# ADC5G_FRONTEND.net
KiCad netlist of a schematic drawn in Altium Designer
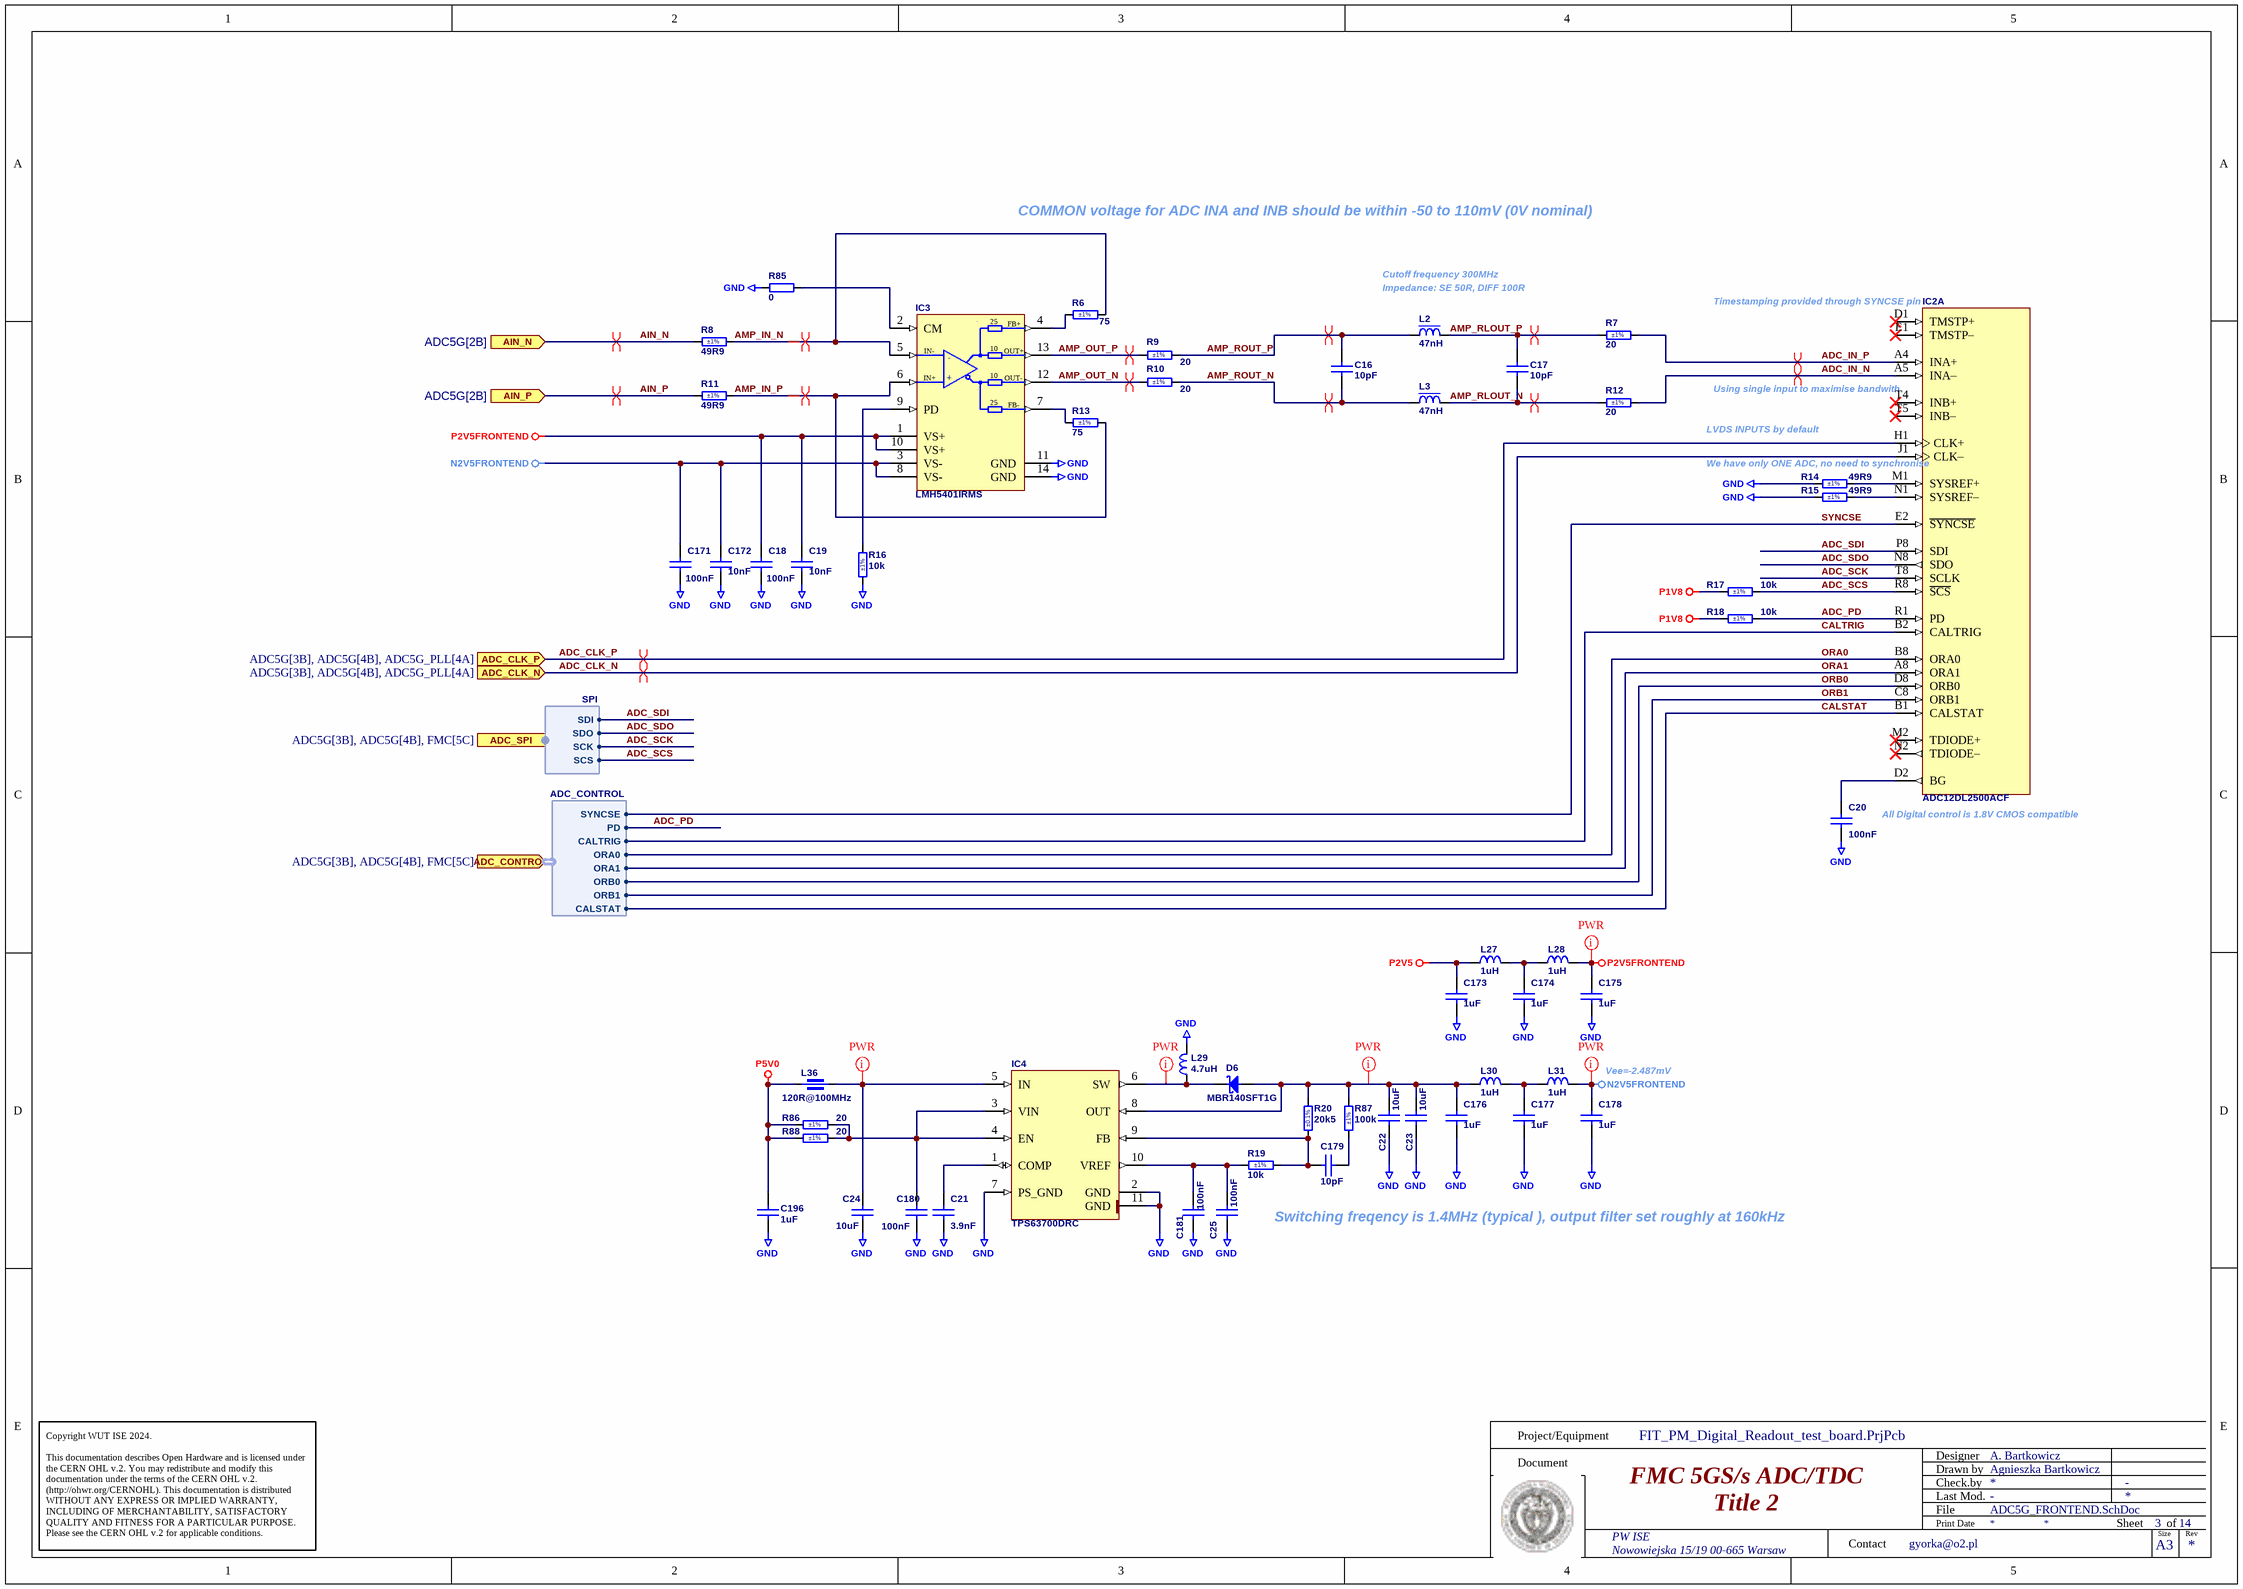
[diagram p0: ADC5G_FRONTEND.SchDoc]

(export (version "E")
  (design (tool "Eeschema 10.0.6"))
  (components
    (comp (ref "C16")
      (value "10pF")
      (footprint "CAPC1005X55N")
      (description "Non-polarised capacitor")
      (fields
        (field (name "PART NUMBER") "CC0402_10PF_50V_5%_C0G")
        (field (name "VOLTAGE") "50V")
        (field (name "AUTHOR") "CERN DEM JLC")
      )
      (libsource (lib "Capacitors") (part "Capacitor - non polarized"))
    )
    (comp (ref "C17")
      (value "10pF")
      (footprint "CAPC1005X55N")
      (description "Non-polarised capacitor")
      (fields
        (field (name "PART NUMBER") "CC0402_10PF_50V_5%_C0G")
        (field (name "VOLTAGE") "50V")
        (field (name "AUTHOR") "CERN DEM JLC")
      )
      (libsource (lib "Capacitors") (part "Capacitor - non polarized"))
    )
    (comp (ref "C18")
      (value "100nF")
      (footprint "CAPC1005X55N")
      (description "Non-polarised capacitor")
      (fields
        (field (name "PART NUMBER") "CC0402_100NF_16V_10%_X5R")
        (field (name "VOLTAGE") "16V")
        (field (name "AUTHOR") "CERN DEM JLC")
      )
      (libsource (lib "Capacitors") (part "Capacitor - non polarized"))
    )
    (comp (ref "C19")
      (value "10nF")
      (footprint "CAPC1005X55N")
      (description "Non-polarised capacitor")
      (fields
        (field (name "PART NUMBER") "CC0402_10NF_50V_10%_X7R")
        (field (name "VOLTAGE") "50V")
        (field (name "AUTHOR") "CERN DEM MR")
      )
      (libsource (lib "Capacitors") (part "Capacitor - non polarized"))
    )
    (comp (ref "C20")
      (value "100nF")
      (footprint "CAPC0603X33N")
      (description "Non-polarised capacitor")
      (fields
        (field (name "PART NUMBER") "CC0201_100NF_6.3V_10%_X7R")
        (field (name "VOLTAGE") "6.3V")
        (field (name "AUTHOR") "CERN DEM BC")
      )
      (libsource (lib "Capacitors") (part "Capacitor - non polarized"))
    )
    (comp (ref "C21")
      (value "3.9nF")
      (footprint "CAPC1005X55N")
      (description "Non-polarised capacitor")
      (fields
        (field (name "PART NUMBER") "CC0402_3.9NF_50V_5%_X7R")
        (field (name "VOLTAGE") "50V")
        (field (name "AUTHOR") "CERN DEM BC")
      )
      (libsource (lib "Capacitors") (part "Capacitor - non polarized"))
    )
    (comp (ref "C22")
      (value "10uF")
      (footprint "CAPC1608X90N")
      (description "Non-polarised capacitor")
      (fields
        (field (name "PART NUMBER") "CC0603_10UF_16V_10%_X5R_MURATA_GRT188R61C106KE13")
        (field (name "VOLTAGE") "16V")
        (field (name "AUTHOR") "CERN DEM HF")
      )
      (libsource (lib "Capacitors") (part "Capacitor - non polarized"))
    )
    (comp (ref "C23")
      (value "10uF")
      (footprint "CAPC1608X90N")
      (description "Non-polarised capacitor")
      (fields
        (field (name "PART NUMBER") "CC0603_10UF_16V_10%_X5R_MURATA_GRT188R61C106KE13")
        (field (name "VOLTAGE") "16V")
        (field (name "AUTHOR") "CERN DEM HF")
      )
      (libsource (lib "Capacitors") (part "Capacitor - non polarized"))
    )
    (comp (ref "C24")
      (value "10uF")
      (footprint "CAPC1608X90N")
      (description "Non-polarised capacitor")
      (fields
        (field (name "PART NUMBER") "CC0603_10UF_16V_10%_X5R_MURATA_GRT188R61C106KE13")
        (field (name "VOLTAGE") "16V")
        (field (name "AUTHOR") "CERN DEM HF")
      )
      (libsource (lib "Capacitors") (part "Capacitor - non polarized"))
    )
    (comp (ref "C25")
      (value "100nF")
      (footprint "CAPC1005X55N")
      (description "Non-polarised capacitor")
      (fields
        (field (name "PART NUMBER") "CC0402_100NF_16V_10%_X5R")
        (field (name "VOLTAGE") "16V")
        (field (name "AUTHOR") "CERN DEM JLC")
      )
      (libsource (lib "Capacitors") (part "Capacitor - non polarized"))
    )
    (comp (ref "C171")
      (value "100nF")
      (footprint "CAPC1005X55N")
      (description "Non-polarised capacitor")
      (fields
        (field (name "PART NUMBER") "CC0402_100NF_16V_10%_X5R")
        (field (name "VOLTAGE") "16V")
        (field (name "AUTHOR") "CERN DEM JLC")
      )
      (libsource (lib "Capacitors") (part "Capacitor - non polarized"))
    )
    (comp (ref "C172")
      (value "10nF")
      (footprint "CAPC1005X55N")
      (description "Non-polarised capacitor")
      (fields
        (field (name "PART NUMBER") "CC0402_10NF_50V_10%_X7R")
        (field (name "VOLTAGE") "50V")
        (field (name "AUTHOR") "CERN DEM MR")
      )
      (libsource (lib "Capacitors") (part "Capacitor - non polarized"))
    )
    (comp (ref "C173")
      (value "1uF")
      (footprint "CAPC1005X55N")
      (description "Non-polarised capacitor")
      (fields
        (field (name "PART NUMBER") "CC0402_1UF_16V_10%_X5R")
        (field (name "VOLTAGE") "16V")
        (field (name "AUTHOR") "CERN DEM JLC")
      )
      (libsource (lib "Capacitors") (part "Capacitor - non polarized"))
    )
    (comp (ref "C174")
      (value "1uF")
      (footprint "CAPC1005X55N")
      (description "Non-polarised capacitor")
      (fields
        (field (name "PART NUMBER") "CC0402_1UF_16V_10%_X5R")
        (field (name "VOLTAGE") "16V")
        (field (name "AUTHOR") "CERN DEM JLC")
      )
      (libsource (lib "Capacitors") (part "Capacitor - non polarized"))
    )
    (comp (ref "C175")
      (value "1uF")
      (footprint "CAPC1005X55N")
      (description "Non-polarised capacitor")
      (fields
        (field (name "PART NUMBER") "CC0402_1UF_16V_10%_X5R")
        (field (name "VOLTAGE") "16V")
        (field (name "AUTHOR") "CERN DEM JLC")
      )
      (libsource (lib "Capacitors") (part "Capacitor - non polarized"))
    )
    (comp (ref "C176")
      (value "1uF")
      (footprint "CAPC1005X55N")
      (description "Non-polarised capacitor")
      (fields
        (field (name "PART NUMBER") "CC0402_1UF_16V_10%_X5R")
        (field (name "VOLTAGE") "16V")
        (field (name "AUTHOR") "CERN DEM JLC")
      )
      (libsource (lib "Capacitors") (part "Capacitor - non polarized"))
    )
    (comp (ref "C177")
      (value "1uF")
      (footprint "CAPC1005X55N")
      (description "Non-polarised capacitor")
      (fields
        (field (name "PART NUMBER") "CC0402_1UF_16V_10%_X5R")
        (field (name "VOLTAGE") "16V")
        (field (name "AUTHOR") "CERN DEM JLC")
      )
      (libsource (lib "Capacitors") (part "Capacitor - non polarized"))
    )
    (comp (ref "C178")
      (value "1uF")
      (footprint "CAPC1005X55N")
      (description "Non-polarised capacitor")
      (fields
        (field (name "PART NUMBER") "CC0402_1UF_16V_10%_X5R")
        (field (name "VOLTAGE") "16V")
        (field (name "AUTHOR") "CERN DEM JLC")
      )
      (libsource (lib "Capacitors") (part "Capacitor - non polarized"))
    )
    (comp (ref "C179")
      (value "10pF")
      (footprint "CAPC1005X55N")
      (description "Non-polarised capacitor")
      (fields
        (field (name "PART NUMBER") "CC0402_10PF_50V_5%_C0G")
        (field (name "VOLTAGE") "50V")
        (field (name "AUTHOR") "CERN DEM JLC")
      )
      (libsource (lib "Capacitors") (part "Capacitor - non polarized"))
    )
    (comp (ref "C180")
      (value "100nF")
      (footprint "CAPC1005X55N")
      (description "Non-polarised capacitor")
      (fields
        (field (name "PART NUMBER") "CC0402_100NF_16V_10%_X5R")
        (field (name "VOLTAGE") "16V")
        (field (name "AUTHOR") "CERN DEM JLC")
      )
      (libsource (lib "Capacitors") (part "Capacitor - non polarized"))
    )
    (comp (ref "C181")
      (value "100nF")
      (footprint "CAPC1005X55N")
      (description "Non-polarised capacitor")
      (fields
        (field (name "PART NUMBER") "CC0402_100NF_16V_10%_X5R")
        (field (name "VOLTAGE") "16V")
        (field (name "AUTHOR") "CERN DEM JLC")
      )
      (libsource (lib "Capacitors") (part "Capacitor - non polarized"))
    )
    (comp (ref "C196")
      (value "1uF")
      (footprint "CAPC1005X55N")
      (description "Non-polarised capacitor")
      (fields
        (field (name "PART NUMBER") "CC0402_1UF_25V_10%_X5R")
        (field (name "VOLTAGE") "25V")
        (field (name "AUTHOR") "CERN DEM BC")
      )
      (libsource (lib "Capacitors") (part "Capacitor - non polarized"))
    )
    (comp (ref "D6")
      (value "MBR140SFT1G")
      (footprint "SOD-123FL")
      (description "Schottky Diode")
      (fields
        (field (name "VOLTAGE") "40V")
        (field (name "POWER") "1A")
        (field (name "AUTHOR") "CERN DEM JLC")
      )
      (libsource (lib "ICs And Semiconductors") (part "Diode Schottky"))
    )
    (comp (ref "IC2")
      (value "ADC12DL2500ACF")
      (footprint "BGA256C100P16X16_1700X1700X331")
      (description "Single-Supply, Multichannel, 125kSPS, 24-Bit, Sigma-Delta ADC with ±10V Inputs")
      (fields (field (name "MANUFACTURER") "TEXAS INSTRUMENTS") (field (name "AUTHOR") "CERN DEM HF"))
      (libsource (lib "ICs And Semiconductors") (part "ADC12DLX500ACF"))
    )
    (comp (ref "IC3")
      (value "LMH5401IRMS")
      (footprint "QFN50P250X250X60-14N")
      (description "Low-Noise, Low-Power, 8-GHz Fully Differential Amplifier")
      (fields (field (name "MANUFACTURER") "TEXAS INSTRUMENTS") (field (name "AUTHOR") "CERN DEM MR"))
      (libsource (lib "ICs And Semiconductors") (part "LMH5401"))
    )
    (comp (ref "IC4")
      (value "TPS63700DRC")
      (footprint "TEXAS_DRC (S-PVSON-N10)")
      (description "DC-DC Inverter")
      (fields (field (name "MANUFACTURER") "TEXAS INSTRUMENTS") (field (name "AUTHOR") "CERN DEM BC"))
      (libsource (lib "ICs And Semiconductors") (part "TPS63700DRC"))
    )
    (comp (ref "L2")
      (value "47nH")
      (footprint "IND_MURATA_LQW15AN_00")
      (description "Inductor With Core")
      (fields
        (field (name "PART NUMBER") "IND0402_47NH_2%_MURATA_LQW15AN47NG00")
        (field (name "POWER") "210mA")
        (field (name "AUTHOR") "CERN DEM HF")
      )
      (libsource (lib "Inductors & Transformers") (part "Inductor With Magnetic core"))
    )
    (comp (ref "L3")
      (value "47nH")
      (footprint "IND_MURATA_LQW15AN_00")
      (description "Inductor With Core")
      (fields
        (field (name "PART NUMBER") "IND0402_47NH_2%_MURATA_LQW15AN47NG00")
        (field (name "POWER") "210mA")
        (field (name "AUTHOR") "CERN DEM HF")
      )
      (libsource (lib "Inductors & Transformers") (part "Inductor With Magnetic core"))
    )
    (comp (ref "L27")
      (value "1uH")
      (footprint "INDC2012X110N")
      (description "Inductor")
      (fields
        (field (name "PART NUMBER") "IND0805_1UH_20%_WURTH_74479775210")
        (field (name "POWER") "800mA")
        (field (name "AUTHOR") "CERN DEM JLC")
      )
      (libsource (lib "Inductors & Transformers") (part "Inductor"))
    )
    (comp (ref "L28")
      (value "1uH")
      (footprint "INDC2012X110N")
      (description "Inductor")
      (fields
        (field (name "PART NUMBER") "IND0805_1UH_20%_WURTH_74479775210")
        (field (name "POWER") "800mA")
        (field (name "AUTHOR") "CERN DEM JLC")
      )
      (libsource (lib "Inductors & Transformers") (part "Inductor"))
    )
    (comp (ref "L29")
      (value "4.7uH")
      (footprint "IND_COILCRAFT_EPL3015")
      (description "Inductor")
      (fields
        (field (name "PART NUMBER") "IND_4.7UH_20%_COILCRAFT_EPL3015")
        (field (name "POWER") "1A")
        (field (name "AUTHOR") "CERN DEM BC")
      )
      (libsource (lib "") (part "Inductor_1"))
    )
    (comp (ref "L30")
      (value "1uH")
      (footprint "INDC2012X110N")
      (description "Inductor")
      (fields
        (field (name "PART NUMBER") "IND0805_1UH_20%_WURTH_74479775210")
        (field (name "POWER") "800mA")
        (field (name "AUTHOR") "CERN DEM JLC")
      )
      (libsource (lib "Inductors & Transformers") (part "Inductor"))
    )
    (comp (ref "L31")
      (value "1uH")
      (footprint "INDC2012X110N")
      (description "Inductor")
      (fields
        (field (name "PART NUMBER") "IND0805_1UH_20%_WURTH_74479775210")
        (field (name "POWER") "800mA")
        (field (name "AUTHOR") "CERN DEM JLC")
      )
      (libsource (lib "Inductors & Transformers") (part "Inductor"))
    )
    (comp (ref "L36")
      (value "120R@100MHz")
      (footprint "INDC1005X55N")
      (fields
        (field (name "PART NUMBER") "IND0402_MURATA_BLM15PX121SN1D")
        (field (name "POWER") "2A")
        (field (name "TOLERANCE") "±25%")
        (field (name "AUTHOR") "CERN DEM JMW")
      )
      (libsource (lib "Inductors & Transformers") (part "Ferrite Bead"))
    )
    (comp (ref "R6")
      (value "75")
      (footprint "RESC1005X40N")
      (description "Resistor - 1%")
      (fields
        (field (name "TOLERANCE") "±1%")
        (field (name "PART NUMBER") "R0402_75R_1%_0.0625W_100PPM")
        (field (name "POWER") "0.0625W")
        (field (name "AUTHOR") "CERN DEM JLC")
      )
      (libsource (lib "Resistors") (part "Resistor - 1%"))
    )
    (comp (ref "R7")
      (value "20")
      (footprint "RESC1005X40N")
      (description "Resistor - 1%")
      (fields
        (field (name "TOLERANCE") "±1%")
        (field (name "PART NUMBER") "R0402_20R_1%_0.0625W_100PPM")
        (field (name "POWER") "0.0625W")
        (field (name "AUTHOR") "CERN DEM JLC")
      )
      (libsource (lib "Resistors") (part "Resistor - 1%"))
    )
    (comp (ref "R8")
      (value "49R9")
      (footprint "RESC1005X40N")
      (description "Resistor - 1%")
      (fields
        (field (name "TOLERANCE") "±1%")
        (field (name "PART NUMBER") "R0402_49R9_1%_0.0625W_100PPM")
        (field (name "POWER") "0.0625W")
        (field (name "AUTHOR") "CERN DEM JLC")
      )
      (libsource (lib "Resistors") (part "Resistor - 1%"))
    )
    (comp (ref "R9")
      (value "20")
      (footprint "RESC1005X40N")
      (description "Resistor - 1%")
      (fields
        (field (name "TOLERANCE") "±1%")
        (field (name "PART NUMBER") "R0402_20R_1%_0.0625W_100PPM")
        (field (name "POWER") "0.0625W")
        (field (name "AUTHOR") "CERN DEM JLC")
      )
      (libsource (lib "Resistors") (part "Resistor - 1%"))
    )
    (comp (ref "R10")
      (value "20")
      (footprint "RESC1005X40N")
      (description "Resistor - 1%")
      (fields
        (field (name "TOLERANCE") "±1%")
        (field (name "PART NUMBER") "R0402_20R_1%_0.0625W_100PPM")
        (field (name "POWER") "0.0625W")
        (field (name "AUTHOR") "CERN DEM JLC")
      )
      (libsource (lib "Resistors") (part "Resistor - 1%"))
    )
    (comp (ref "R11")
      (value "49R9")
      (footprint "RESC1005X40N")
      (description "Resistor - 1%")
      (fields
        (field (name "TOLERANCE") "±1%")
        (field (name "PART NUMBER") "R0402_49R9_1%_0.0625W_100PPM")
        (field (name "POWER") "0.0625W")
        (field (name "AUTHOR") "CERN DEM JLC")
      )
      (libsource (lib "Resistors") (part "Resistor - 1%"))
    )
    (comp (ref "R12")
      (value "20")
      (footprint "RESC1005X40N")
      (description "Resistor - 1%")
      (fields
        (field (name "TOLERANCE") "±1%")
        (field (name "PART NUMBER") "R0402_20R_1%_0.0625W_100PPM")
        (field (name "POWER") "0.0625W")
        (field (name "AUTHOR") "CERN DEM JLC")
      )
      (libsource (lib "Resistors") (part "Resistor - 1%"))
    )
    (comp (ref "R13")
      (value "75")
      (footprint "RESC1005X40N")
      (description "Resistor - 1%")
      (fields
        (field (name "TOLERANCE") "±1%")
        (field (name "PART NUMBER") "R0402_75R_1%_0.0625W_100PPM")
        (field (name "POWER") "0.0625W")
        (field (name "AUTHOR") "CERN DEM JLC")
      )
      (libsource (lib "Resistors") (part "Resistor - 1%"))
    )
    (comp (ref "R14")
      (value "49R9")
      (footprint "RESC1005X40N")
      (description "Resistor - 1%")
      (fields
        (field (name "TOLERANCE") "±1%")
        (field (name "PART NUMBER") "R0402_49R9_1%_0.0625W_100PPM")
        (field (name "POWER") "0.0625W")
        (field (name "AUTHOR") "CERN DEM JLC")
      )
      (libsource (lib "Resistors") (part "Resistor - 1%"))
    )
    (comp (ref "R15")
      (value "49R9")
      (footprint "RESC1005X40N")
      (description "Resistor - 1%")
      (fields
        (field (name "TOLERANCE") "±1%")
        (field (name "PART NUMBER") "R0402_49R9_1%_0.0625W_100PPM")
        (field (name "POWER") "0.0625W")
        (field (name "AUTHOR") "CERN DEM JLC")
      )
      (libsource (lib "Resistors") (part "Resistor - 1%"))
    )
    (comp (ref "R16")
      (value "10k")
      (footprint "RESC1005X40N")
      (description "Resistor - 1%")
      (fields
        (field (name "TOLERANCE") "±1%")
        (field (name "PART NUMBER") "R0402_10K_1%_0.0625W_100PPM")
        (field (name "POWER") "0.0625W")
        (field (name "AUTHOR") "CERN DEM JLC")
      )
      (libsource (lib "Resistors") (part "Resistor - 1%"))
    )
    (comp (ref "R17")
      (value "10k")
      (footprint "RESC1005X40N")
      (description "Resistor - 1%")
      (fields
        (field (name "TOLERANCE") "±1%")
        (field (name "PART NUMBER") "R0402_10K_1%_0.0625W_100PPM")
        (field (name "POWER") "0.0625W")
        (field (name "AUTHOR") "CERN DEM JLC")
      )
      (libsource (lib "Resistors") (part "Resistor - 1%"))
    )
    (comp (ref "R18")
      (value "10k")
      (footprint "RESC1005X40N")
      (description "Resistor - 1%")
      (fields
        (field (name "TOLERANCE") "±1%")
        (field (name "PART NUMBER") "R0402_10K_1%_0.0625W_100PPM")
        (field (name "POWER") "0.0625W")
        (field (name "AUTHOR") "CERN DEM JLC")
      )
      (libsource (lib "Resistors") (part "Resistor - 1%"))
    )
    (comp (ref "R19")
      (value "10k")
      (footprint "RESC1005X40N")
      (description "Resistor - 1%")
      (fields
        (field (name "TOLERANCE") "±1%")
        (field (name "PART NUMBER") "R0402_10K_1%_0.0625W_100PPM")
        (field (name "POWER") "0.0625W")
        (field (name "AUTHOR") "CERN DEM JLC")
      )
      (libsource (lib "Resistors") (part "Resistor - 1%"))
    )
    (comp (ref "R20")
      (value "20k5")
      (footprint "RESC1608X55N")
      (description "Resistor - 0.1%")
      (fields
        (field (name "TOLERANCE") "±0.1%")
        (field (name "PART NUMBER") "R0603_20K5_0.1%_0.063W_10PPM")
        (field (name "POWER") "0.063W")
        (field (name "AUTHOR") "CERN DEM JLC")
      )
      (libsource (lib "Resistors") (part "Resistor - 0.1%"))
    )
    (comp (ref "R85")
      (value "0")
      (footprint "RESC1005X40N")
      (description "Resistor")
      (fields
        (field (name "PART NUMBER") "R0402_0R_JUMPER")
        (field (name "MANUFACTURER") "GENERIC")
        (field (name "AUTHOR") "CERN DEM JLC")
      )
      (libsource (lib "Resistors") (part "Resistor"))
    )
    (comp (ref "R86")
      (value "20")
      (footprint "RESC1005X40N")
      (description "Resistor - 1%")
      (fields
        (field (name "TOLERANCE") "±1%")
        (field (name "PART NUMBER") "R0402_20R_1%_0.0625W_100PPM")
        (field (name "POWER") "0.0625W")
        (field (name "AUTHOR") "CERN DEM JLC")
      )
      (libsource (lib "Resistors") (part "Resistor - 1%"))
    )
    (comp (ref "R87")
      (value "100k")
      (footprint "RESC1005X40N")
      (description "Resistor - 1%")
      (fields
        (field (name "TOLERANCE") "±1%")
        (field (name "PART NUMBER") "R0402_100K_1%_0.0625W_100PPM")
        (field (name "POWER") "0.0625W")
        (field (name "AUTHOR") "CERN DEM JLC")
      )
      (libsource (lib "Resistors") (part "Resistor - 1%"))
    )
    (comp (ref "R88")
      (value "20")
      (footprint "RESC1005X40N")
      (description "Resistor - 1%")
      (fields
        (field (name "TOLERANCE") "±1%")
        (field (name "PART NUMBER") "R0402_20R_1%_0.0625W_100PPM")
        (field (name "POWER") "0.0625W")
        (field (name "AUTHOR") "CERN DEM JLC")
      )
      (libsource (lib "Resistors") (part "Resistor - 1%"))
    )
  )
  (nets
    (net (code "3") (name "/ADC_CLK_N") (class "Default")
      (node (ref "IC2") (pin "J1") (pinfunction "CLK–_J1") (pintype "input"))
    )
    (net (code "4") (name "/ADC_CLK_P") (class "Default")
      (node (ref "IC2") (pin "H1") (pinfunction "CLK+_H1") (pintype "input"))
    )
    (net (code "5") (name "/ADC_IN_N") (class "Default")
      (node (ref "IC2") (pin "A5") (pinfunction "INA–_A5") (pintype "input"))
      (node (ref "R12") (pin "2") (pinfunction "2_2") (pintype "passive"))
    )
    (net (code "6") (name "/ADC_IN_P") (class "Default")
      (node (ref "IC2") (pin "A4") (pinfunction "INA+_A4") (pintype "input"))
      (node (ref "R7") (pin "2") (pinfunction "2_2") (pintype "passive"))
    )
    (net (code "7") (name "/ADC_PD") (class "Default")
      (node (ref "IC2") (pin "R1") (pinfunction "PD_R1") (pintype "input"))
      (node (ref "R18") (pin "2") (pinfunction "2_2") (pintype "passive"))
    )
    (net (code "8") (name "/ADC_SCK") (class "Default")
      (node (ref "IC2") (pin "T8") (pinfunction "SCLK_T8") (pintype "input"))
    )
    (net (code "9") (name "/ADC_SCS") (class "Default")
      (node (ref "IC2") (pin "R8") (pinfunction "~{SCS}_R8") (pintype "input"))
      (node (ref "R17") (pin "2") (pinfunction "2_2") (pintype "passive"))
    )
    (net (code "10") (name "/ADC_SDI") (class "Default")
      (node (ref "IC2") (pin "P8") (pinfunction "SDI_P8") (pintype "input"))
    )
    (net (code "11") (name "/ADC_SDO") (class "Default")
      (node (ref "IC2") (pin "N8") (pinfunction "SDO_N8") (pintype "output"))
    )
    (net (code "12") (name "/AIN_N") (class "Default")
      (node (ref "R8") (pin "1") (pinfunction "1_1") (pintype "passive"))
    )
    (net (code "13") (name "/AIN_P") (class "Default")
      (node (ref "R11") (pin "1") (pinfunction "1_1") (pintype "passive"))
    )
    (net (code "14") (name "/AMP_IN_N") (class "Default")
      (node (ref "IC3") (pin "5") (pinfunction "IN-_5") (pintype "input"))
      (node (ref "R6") (pin "2") (pinfunction "2_2") (pintype "passive"))
      (node (ref "R8") (pin "2") (pinfunction "2_2") (pintype "passive"))
    )
    (net (code "15") (name "/AMP_IN_P") (class "Default")
      (node (ref "IC3") (pin "6") (pinfunction "IN+_6") (pintype "input"))
      (node (ref "R11") (pin "2") (pinfunction "2_2") (pintype "passive"))
      (node (ref "R13") (pin "2") (pinfunction "2_2") (pintype "passive"))
    )
    (net (code "16") (name "/AMP_OUT_N") (class "Default")
      (node (ref "IC3") (pin "12") (pinfunction "OUT-_12") (pintype "output"))
      (node (ref "R10") (pin "1") (pinfunction "1_1") (pintype "passive"))
    )
    (net (code "17") (name "/AMP_OUT_P") (class "Default")
      (node (ref "IC3") (pin "13") (pinfunction "OUT+_13") (pintype "output"))
      (node (ref "R9") (pin "1") (pinfunction "1_1") (pintype "passive"))
    )
    (net (code "18") (name "/AMP_RLOUT_N") (class "Default")
      (node (ref "C17") (pin "1") (pinfunction "1_1") (pintype "passive"))
      (node (ref "L3") (pin "2") (pinfunction "2_2") (pintype "passive"))
      (node (ref "R12") (pin "1") (pinfunction "1_1") (pintype "passive"))
    )
    (net (code "19") (name "/AMP_RLOUT_P") (class "Default")
      (node (ref "C17") (pin "2") (pinfunction "2_2") (pintype "passive"))
      (node (ref "L2") (pin "2") (pinfunction "2_2") (pintype "passive"))
      (node (ref "R7") (pin "1") (pinfunction "1_1") (pintype "passive"))
    )
    (net (code "20") (name "/AMP_ROUT_N") (class "Default")
      (node (ref "C16") (pin "1") (pinfunction "1_1") (pintype "passive"))
      (node (ref "L3") (pin "1") (pinfunction "1_1") (pintype "passive"))
      (node (ref "R10") (pin "2") (pinfunction "2_2") (pintype "passive"))
    )
    (net (code "21") (name "/AMP_ROUT_P") (class "Default")
      (node (ref "C16") (pin "2") (pinfunction "2_2") (pintype "passive"))
      (node (ref "L2") (pin "1") (pinfunction "1_1") (pintype "passive"))
      (node (ref "R9") (pin "2") (pinfunction "2_2") (pintype "passive"))
    )
    (net (code "22") (name "/CALSTAT") (class "Default")
      (node (ref "IC2") (pin "B1") (pinfunction "CALSTAT_B1") (pintype "input"))
    )
    (net (code "23") (name "/CALTRIG") (class "Default")
      (node (ref "IC2") (pin "B2") (pinfunction "CALTRIG_B2") (pintype "input"))
    )
    (net (code "24") (name "/ORA0") (class "Default")
      (node (ref "IC2") (pin "B8") (pinfunction "ORA0_B8") (pintype "input"))
    )
    (net (code "25") (name "/ORA1") (class "Default")
      (node (ref "IC2") (pin "A8") (pinfunction "ORA1_A8") (pintype "input"))
    )
    (net (code "26") (name "/ORB0") (class "Default")
      (node (ref "IC2") (pin "D8") (pinfunction "ORB0_D8") (pintype "input"))
    )
    (net (code "27") (name "/ORB1") (class "Default")
      (node (ref "IC2") (pin "C8") (pinfunction "ORB1_C8") (pintype "input"))
    )
    (net (code "28") (name "/SYNCSE") (class "Default")
      (node (ref "IC2") (pin "E2") (pinfunction "~{SYNCSE}_E2") (pintype "input"))
    )
    (net (code "31") (name "GND") (class "Default")
      (node (ref "C171") (pin "1") (pinfunction "1_1") (pintype "passive"))
      (node (ref "C172") (pin "1") (pinfunction "1_1") (pintype "passive"))
      (node (ref "C173") (pin "1") (pinfunction "1_1") (pintype "passive"))
      (node (ref "C174") (pin "1") (pinfunction "1_1") (pintype "passive"))
      (node (ref "C175") (pin "1") (pinfunction "1_1") (pintype "passive"))
      (node (ref "C176") (pin "1") (pinfunction "1_1") (pintype "passive"))
      (node (ref "C177") (pin "1") (pinfunction "1_1") (pintype "passive"))
      (node (ref "C178") (pin "1") (pinfunction "1_1") (pintype "passive"))
      (node (ref "C18") (pin "1") (pinfunction "1_1") (pintype "passive"))
      (node (ref "C180") (pin "1") (pinfunction "1_1") (pintype "passive"))
      (node (ref "C181") (pin "1") (pinfunction "1_1") (pintype "passive"))
      (node (ref "C19") (pin "1") (pinfunction "1_1") (pintype "passive"))
      (node (ref "C196") (pin "1") (pinfunction "1_1") (pintype "passive"))
      (node (ref "C20") (pin "1") (pinfunction "1_1") (pintype "passive"))
      (node (ref "C21") (pin "1") (pinfunction "1_1") (pintype "passive"))
      (node (ref "C22") (pin "1") (pinfunction "1_1") (pintype "passive"))
      (node (ref "C23") (pin "1") (pinfunction "1_1") (pintype "passive"))
      (node (ref "C24") (pin "1") (pinfunction "1_1") (pintype "passive"))
      (node (ref "C25") (pin "1") (pinfunction "1_1") (pintype "passive"))
      (node (ref "IC3") (pin "11") (pinfunction "GND_11") (pintype "power_in"))
      (node (ref "IC3") (pin "14") (pinfunction "GND_14") (pintype "power_in"))
      (node (ref "IC4") (pin "11") (pinfunction "GND_11") (pintype "power_in"))
      (node (ref "IC4") (pin "2") (pinfunction "GND_2") (pintype "power_in"))
      (node (ref "IC4") (pin "7") (pinfunction "PS_GND_7") (pintype "input"))
      (node (ref "L29") (pin "2") (pinfunction "2_2") (pintype "passive"))
      (node (ref "R14") (pin "1") (pinfunction "1_1") (pintype "passive"))
      (node (ref "R15") (pin "1") (pinfunction "1_1") (pintype "passive"))
      (node (ref "R16") (pin "1") (pinfunction "1_1") (pintype "passive"))
      (node (ref "R85") (pin "1") (pinfunction "1_1") (pintype "passive"))
    )
    (net (code "32") (name "N2V5FRONTEND") (class "Default")
      (node (ref "C171") (pin "2") (pinfunction "2_2") (pintype "passive"))
      (node (ref "C172") (pin "2") (pinfunction "2_2") (pintype "passive"))
      (node (ref "C178") (pin "2") (pinfunction "2_2") (pintype "passive"))
      (node (ref "IC3") (pin "3") (pinfunction "VS-_3") (pintype "power_in"))
      (node (ref "IC3") (pin "8") (pinfunction "VS-_8") (pintype "power_in"))
      (node (ref "L31") (pin "2") (pinfunction "2_2") (pintype "passive"))
    )
    (net (code "33") (name "Net-(C174-Pad2)") (class "Default")
      (node (ref "C174") (pin "2") (pinfunction "2_2") (pintype "passive"))
      (node (ref "L27") (pin "2") (pinfunction "2_2") (pintype "passive"))
      (node (ref "L28") (pin "1") (pinfunction "1_1") (pintype "passive"))
    )
    (net (code "34") (name "Net-(C177-Pad2)") (class "Default")
      (node (ref "C177") (pin "2") (pinfunction "2_2") (pintype "passive"))
      (node (ref "L30") (pin "2") (pinfunction "2_2") (pintype "passive"))
      (node (ref "L31") (pin "1") (pinfunction "1_1") (pintype "passive"))
    )
    (net (code "35") (name "Net-(C179-Pad2)") (class "Default")
      (node (ref "C179") (pin "2") (pinfunction "2_2") (pintype "passive"))
      (node (ref "R87") (pin "1") (pinfunction "1_1") (pintype "passive"))
    )
    (net (code "36") (name "Net-(D6-A)") (class "Default")
      (node (ref "C176") (pin "2") (pinfunction "2_2") (pintype "passive"))
      (node (ref "C22") (pin "2") (pinfunction "2_2") (pintype "passive"))
      (node (ref "C23") (pin "2") (pinfunction "2_2") (pintype "passive"))
      (node (ref "D6") (pin "2") (pinfunction "A_2") (pintype "passive"))
      (node (ref "IC4") (pin "8") (pinfunction "OUT_8") (pintype "input"))
      (node (ref "L30") (pin "1") (pinfunction "1_1") (pintype "passive"))
      (node (ref "R20") (pin "1") (pinfunction "1_1") (pintype "passive"))
      (node (ref "R87") (pin "2") (pinfunction "2_2") (pintype "passive"))
    )
    (net (code "37") (name "Net-(D6-C)") (class "Default")
      (node (ref "D6") (pin "1") (pinfunction "C_1") (pintype "passive"))
      (node (ref "IC4") (pin "6") (pinfunction "SW_6") (pintype "output"))
      (node (ref "L29") (pin "1") (pinfunction "1_1") (pintype "passive"))
    )
    (net (code "38") (name "Net-(IC2A-BG)") (class "Default")
      (node (ref "C20") (pin "2") (pinfunction "2_2") (pintype "passive"))
      (node (ref "IC2") (pin "D2") (pinfunction "BG_D2") (pintype "output"))
    )
    (net (code "39") (name "Net-(IC2A-SYSREF+)") (class "Default")
      (node (ref "IC2") (pin "M1") (pinfunction "SYSREF+_M1") (pintype "input"))
      (node (ref "R14") (pin "2") (pinfunction "2_2") (pintype "passive"))
    )
    (net (code "40") (name "Net-(IC2A-SYSREF–)") (class "Default")
      (node (ref "IC2") (pin "N1") (pinfunction "SYSREF–_N1") (pintype "input"))
      (node (ref "R15") (pin "2") (pinfunction "2_2") (pintype "passive"))
    )
    (net (code "41") (name "Net-(IC3-CM)") (class "Default")
      (node (ref "IC3") (pin "2") (pinfunction "CM_2") (pintype "input"))
      (node (ref "R85") (pin "2") (pinfunction "2_2") (pintype "passive"))
    )
    (net (code "42") (name "Net-(IC3-FB+)") (class "Default")
      (node (ref "IC3") (pin "4") (pinfunction "FB+_4") (pintype "output"))
      (node (ref "R6") (pin "1") (pinfunction "1_1") (pintype "passive"))
    )
    (net (code "43") (name "Net-(IC3-FB-)") (class "Default")
      (node (ref "IC3") (pin "7") (pinfunction "FB-_7") (pintype "output"))
      (node (ref "R13") (pin "1") (pinfunction "1_1") (pintype "passive"))
    )
    (net (code "44") (name "Net-(IC3-PD)") (class "Default")
      (node (ref "IC3") (pin "9") (pinfunction "PD_9") (pintype "input"))
      (node (ref "R16") (pin "2") (pinfunction "2_2") (pintype "passive"))
    )
    (net (code "45") (name "Net-(IC4-COMP)") (class "Default")
      (node (ref "C21") (pin "2") (pinfunction "2_2") (pintype "passive"))
      (node (ref "IC4") (pin "1") (pinfunction "COMP_1") (pintype "bidirectional"))
    )
    (net (code "46") (name "Net-(IC4-EN)") (class "Default")
      (node (ref "C180") (pin "2") (pinfunction "2_2") (pintype "passive"))
      (node (ref "IC4") (pin "3") (pinfunction "VIN_3") (pintype "input"))
      (node (ref "IC4") (pin "4") (pinfunction "EN_4") (pintype "input"))
      (node (ref "R86") (pin "1") (pinfunction "1_1") (pintype "passive"))
      (node (ref "R88") (pin "1") (pinfunction "1_1") (pintype "passive"))
    )
    (net (code "47") (name "Net-(IC4-FB)") (class "Default")
      (node (ref "C179") (pin "1") (pinfunction "1_1") (pintype "passive"))
      (node (ref "IC4") (pin "9") (pinfunction "FB_9") (pintype "input"))
      (node (ref "R19") (pin "2") (pinfunction "2_2") (pintype "passive"))
      (node (ref "R20") (pin "2") (pinfunction "2_2") (pintype "passive"))
    )
    (net (code "48") (name "Net-(IC4-IN)") (class "Default")
      (node (ref "C24") (pin "2") (pinfunction "2_2") (pintype "passive"))
      (node (ref "IC4") (pin "5") (pinfunction "IN_5") (pintype "input"))
      (node (ref "L36") (pin "2") (pinfunction "2_2") (pintype "passive"))
    )
    (net (code "49") (name "Net-(IC4-VREF)") (class "Default")
      (node (ref "C181") (pin "2") (pinfunction "2_2") (pintype "passive"))
      (node (ref "C25") (pin "2") (pinfunction "2_2") (pintype "passive"))
      (node (ref "IC4") (pin "10") (pinfunction "VREF_10") (pintype "output"))
      (node (ref "R19") (pin "1") (pinfunction "1_1") (pintype "passive"))
    )
    (net (code "50") (name "P1V8") (class "Default")
      (node (ref "R17") (pin "1") (pinfunction "1_1") (pintype "passive"))
      (node (ref "R18") (pin "1") (pinfunction "1_1") (pintype "passive"))
    )
    (net (code "51") (name "P2V5") (class "Default")
      (node (ref "C173") (pin "2") (pinfunction "2_2") (pintype "passive"))
      (node (ref "L27") (pin "1") (pinfunction "1_1") (pintype "passive"))
    )
    (net (code "52") (name "P2V5FRONTEND") (class "Default")
      (node (ref "C175") (pin "2") (pinfunction "2_2") (pintype "passive"))
      (node (ref "C18") (pin "2") (pinfunction "2_2") (pintype "passive"))
      (node (ref "C19") (pin "2") (pinfunction "2_2") (pintype "passive"))
      (node (ref "IC3") (pin "1") (pinfunction "VS+_1") (pintype "power_in"))
      (node (ref "IC3") (pin "10") (pinfunction "VS+_10") (pintype "power_in"))
      (node (ref "L28") (pin "2") (pinfunction "2_2") (pintype "passive"))
    )
    (net (code "53") (name "P5V0") (class "Default")
      (node (ref "C196") (pin "2") (pinfunction "2_2") (pintype "passive"))
      (node (ref "L36") (pin "1") (pinfunction "1_1") (pintype "passive"))
      (node (ref "R86") (pin "2") (pinfunction "2_2") (pintype "passive"))
      (node (ref "R88") (pin "2") (pinfunction "2_2") (pintype "passive"))
    )
    (net (code "54") (name "unconnected-(IC2A-INB+-PadT4)") (class "Default")
      (node (ref "IC2") (pin "T4") (pinfunction "INB+_T4") (pintype "input+no_connect"))
    )
    (net (code "55") (name "unconnected-(IC2A-INB–-PadT5)") (class "Default")
      (node (ref "IC2") (pin "T5") (pinfunction "INB–_T5") (pintype "input+no_connect"))
    )
    (net (code "56") (name "unconnected-(IC2A-TDIODE+-PadM2)") (class "Default")
      (node (ref "IC2") (pin "M2") (pinfunction "TDIODE+_M2") (pintype "input+no_connect"))
    )
    (net (code "57") (name "unconnected-(IC2A-TDIODE–-PadN2)") (class "Default")
      (node (ref "IC2") (pin "N2") (pinfunction "TDIODE–_N2") (pintype "output+no_connect"))
    )
    (net (code "58") (name "unconnected-(IC2A-TMSTP+-PadD1)") (class "Default")
      (node (ref "IC2") (pin "D1") (pinfunction "TMSTP+_D1") (pintype "input+no_connect"))
    )
    (net (code "59") (name "unconnected-(IC2A-TMSTP–-PadE1)") (class "Default")
      (node (ref "IC2") (pin "E1") (pinfunction "TMSTP–_E1") (pintype "input+no_connect"))
    )
  )
)
